# Power_schematic.net
KiCad netlist of a schematic drawn in Altium Designer
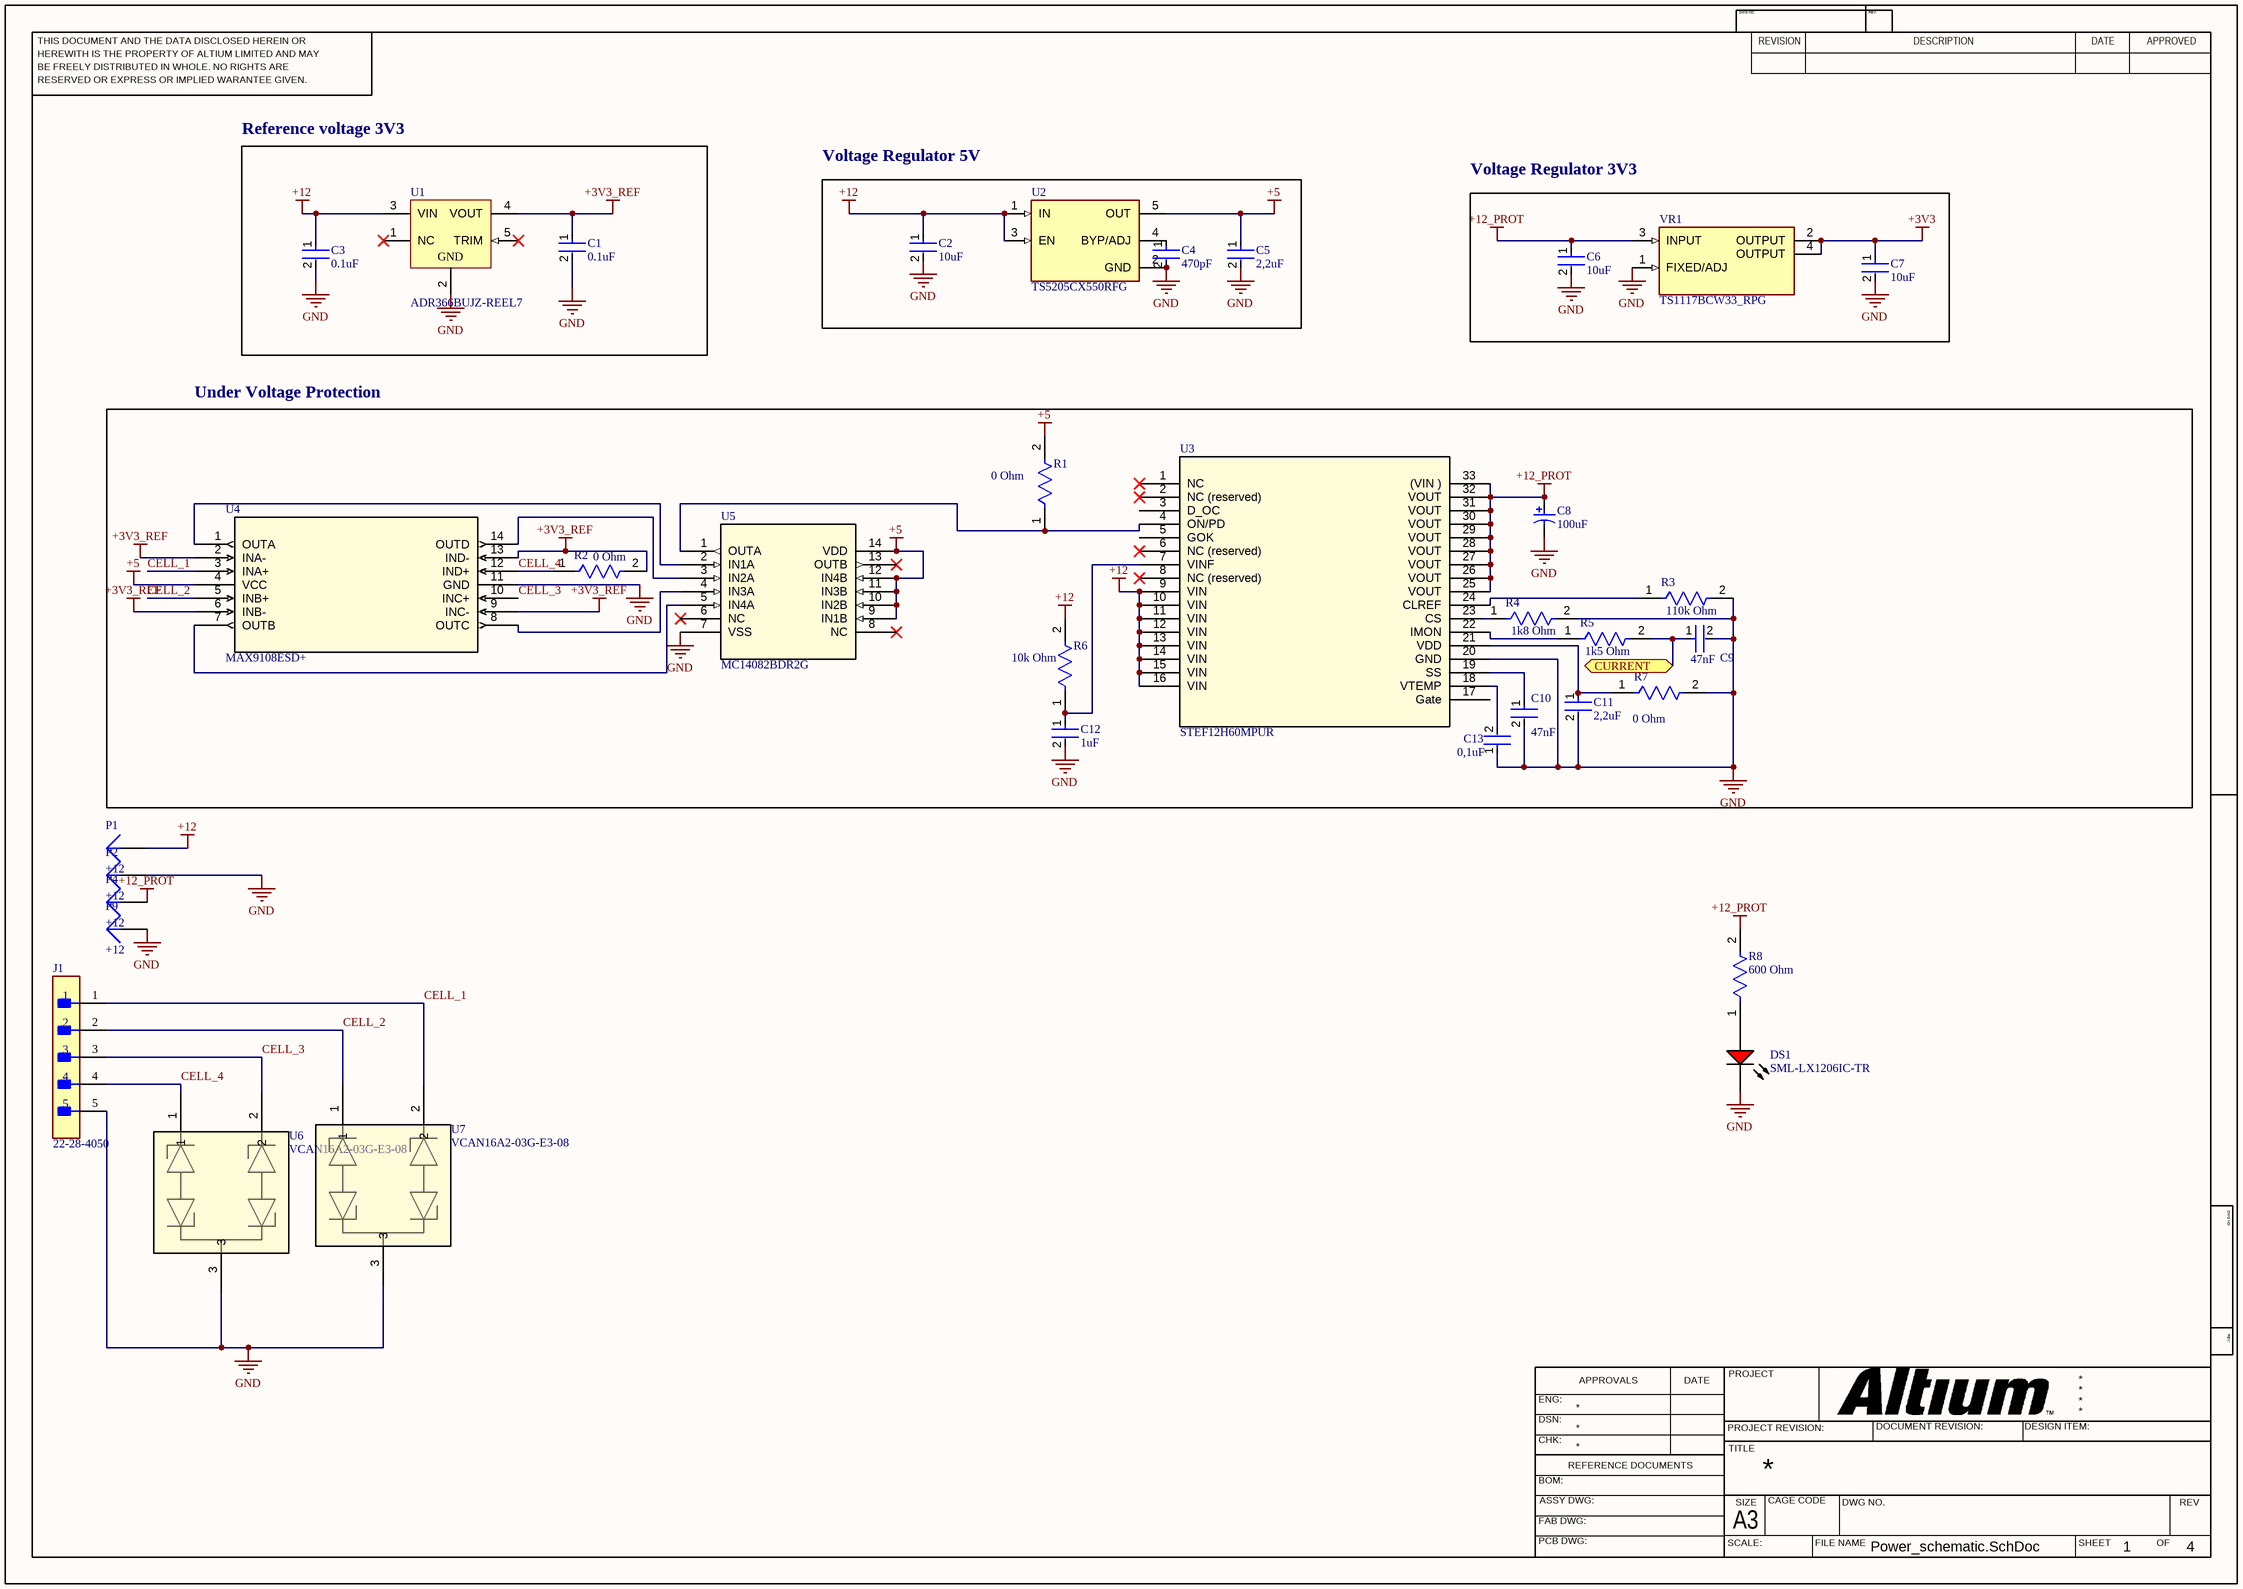
[diagram p0: Power_schematic.SchDoc]

(export (version "E")
  (design (tool "Eeschema 10.0.6"))
  (components
    (comp (ref "C1")
      (value "0.1uF")
      (footprint "FP-CC0805-0_85-MFG")
      (description "CAP CER 0.1UF 50V X7R 0805")
      (fields (field (name "TOLERANCE") "0.1") (field (name "MANUFACTURER PART NUMBER") "CC0805KRX7R9BB104"))
      (libsource (lib "Altium Content Vault") (part "11868f565c42a9108669ba33697ecf6"))
    )
    (comp (ref "C2")
      (value "10uF")
      (footprint "FP-CC0805-0_85-MFG")
      (description "CAP CER 0.1UF 50V X7R 0805")
      (fields (field (name "TOLERANCE") "0.1") (field (name "MANUFACTURER PART NUMBER") "CC0805KRX7R9BB104"))
      (libsource (lib "Altium Content Vault") (part "11868f565c42a9108669ba33697ecf6"))
    )
    (comp (ref "C3")
      (value "0.1uF")
      (footprint "FP-CC0805-0_85-MFG")
      (description "CAP CER 0.1UF 50V X7R 0805")
      (fields (field (name "TOLERANCE") "0.1") (field (name "MANUFACTURER PART NUMBER") "CC0805KRX7R9BB104"))
      (libsource (lib "Altium Content Vault") (part "11868f565c42a9108669ba33697ecf6"))
    )
    (comp (ref "C4")
      (value "470pF")
      (footprint "FP-CC0805-0_85-MFG")
      (description "CAP CER 0.1UF 50V X7R 0805")
      (fields (field (name "TOLERANCE") "0.1") (field (name "MANUFACTURER PART NUMBER") "CC0805KRX7R9BB104"))
      (libsource (lib "Altium Content Vault") (part "11868f565c42a9108669ba33697ecf6"))
    )
    (comp (ref "C5")
      (value "2,2uF")
      (footprint "FP-CC0805-0_85-MFG")
      (description "CAP CER 0.1UF 50V X7R 0805")
      (fields (field (name "TOLERANCE") "0.1") (field (name "MANUFACTURER PART NUMBER") "CC0805KRX7R9BB104"))
      (libsource (lib "Altium Content Vault") (part "11868f565c42a9108669ba33697ecf6"))
    )
    (comp (ref "C6")
      (value "10uF")
      (footprint "FP-CC0805-0_85-MFG")
      (description "CAP CER 0.1UF 50V X7R 0805")
      (fields (field (name "TOLERANCE") "0.1") (field (name "MANUFACTURER PART NUMBER") "CC0805KRX7R9BB104"))
      (libsource (lib "Altium Content Vault") (part "11868f565c42a9108669ba33697ecf6"))
    )
    (comp (ref "C7")
      (value "10uF")
      (footprint "FP-CC0805-0_85-MFG")
      (description "CAP CER 0.1UF 50V X7R 0805")
      (fields (field (name "TOLERANCE") "0.1") (field (name "MANUFACTURER PART NUMBER") "CC0805KRX7R9BB104"))
      (libsource (lib "Altium Content Vault") (part "11868f565c42a9108669ba33697ecf6"))
    )
    (comp (ref "C8")
      (value "100uF")
      (footprint "PNSC-FK-V-D8_V")
      (fields (field (name "MANUFACTURER") "Panasonic"))
      (libsource (lib "Altium Content Vault") (part "CAP-P-2"))
    )
    (comp (ref "C9")
      (value "47nF")
      (footprint "FP-CC0805-0_85-MFG")
      (description "CAP CER 0.1UF 50V X7R 0805")
      (fields (field (name "TOLERANCE") "0.1") (field (name "MANUFACTURER PART NUMBER") "CC0805KRX7R9BB104"))
      (libsource (lib "Altium Content Vault") (part "11868f565c42a9108669ba33697ecf6"))
    )
    (comp (ref "C10")
      (value "47nF")
      (footprint "FP-CC0805-0_85-MFG")
      (description "CAP CER 0.1UF 50V X7R 0805")
      (fields (field (name "TOLERANCE") "0.1") (field (name "MANUFACTURER PART NUMBER") "CC0805KRX7R9BB104"))
      (libsource (lib "Altium Content Vault") (part "11868f565c42a9108669ba33697ecf6"))
    )
    (comp (ref "C11")
      (value "2,2uF")
      (footprint "FP-CC0805-0_85-MFG")
      (description "CAP CER 0.1UF 50V X7R 0805")
      (fields (field (name "TOLERANCE") "0.1") (field (name "MANUFACTURER PART NUMBER") "CC0805KRX7R9BB104"))
      (libsource (lib "Altium Content Vault") (part "11868f565c42a9108669ba33697ecf6"))
    )
    (comp (ref "C12")
      (value "1uF")
      (footprint "FP-CC0805-0_85-MFG")
      (description "CAP CER 0.1UF 50V X7R 0805")
      (fields (field (name "TOLERANCE") "0.1") (field (name "MANUFACTURER PART NUMBER") "CC0805KRX7R9BB104"))
      (libsource (lib "Altium Content Vault") (part "11868f565c42a9108669ba33697ecf6"))
    )
    (comp (ref "C13")
      (value "0,1uF")
      (footprint "FP-CC0805-0_85-MFG")
      (description "CAP CER 0.1UF 50V X7R 0805")
      (fields (field (name "TOLERANCE") "0.1") (field (name "MANUFACTURER PART NUMBER") "CC0805KRX7R9BB104"))
      (libsource (lib "Altium Content Vault") (part "11868f565c42a9108669ba33697ecf6"))
    )
    (comp (ref "DS1")
      (value "SML-LX1206IC-TR")
      (footprint "LUMX-SML-LX1206IC_V")
      (description "LED Red, 65 mW, -40 to 85 degC, 2-Pin SMD, RoHS, Tape and Reel")
      (fields (field (name "MANUFACTURER") "Lumex"))
      (libsource (lib "Altium Content Vault") (part "LED-RED-AK-2"))
    )
    (comp (ref "J1")
      (value "22-28-4050")
      (footprint "FP-22-28-4050-MFG")
      (libsource (lib "Altium Content Vault") (part "bf93c07fd2649a848d0ec8585582aab"))
    )
    (comp (ref "P1")
      (value "+12")
      (footprint "PIN1")
      (description "Plug")
      (fields (field (name "PUBLISHER") "Altium Limited"))
      (libsource (lib "Miscellaneous Connectors") (part "Plug"))
    )
    (comp (ref "P2")
      (value "+12")
      (footprint "PIN1")
      (description "Plug")
      (fields (field (name "PUBLISHER") "Altium Limited"))
      (libsource (lib "Miscellaneous Connectors") (part "Plug"))
    )
    (comp (ref "P4")
      (value "+12")
      (footprint "PIN1")
      (description "Plug")
      (fields (field (name "PUBLISHER") "Altium Limited"))
      (libsource (lib "Miscellaneous Connectors") (part "Plug"))
    )
    (comp (ref "P9")
      (value "+12")
      (footprint "PIN1")
      (description "Plug")
      (fields (field (name "PUBLISHER") "Altium Limited"))
      (libsource (lib "Miscellaneous Connectors") (part "Plug"))
    )
    (comp (ref "R1")
      (value "0 Ohm")
      (footprint "FP-RMCF0805-MFG")
      (description "RES 0 OHM JUMPER 1/8W 0805")
      (libsource (lib "Altium Content Vault") (part "1029c3af85768c4190bb7ad29bc67b5"))
    )
    (comp (ref "R2")
      (value "0 Ohm")
      (footprint "FP-RMCF0805-MFG")
      (description "RES 0 OHM JUMPER 1/8W 0805")
      (libsource (lib "Altium Content Vault") (part "1029c3af85768c4190bb7ad29bc67b5"))
    )
    (comp (ref "R3")
      (value "110k Ohm")
      (footprint "FP-RMCF0805-MFG")
      (description "RES 0 OHM JUMPER 1/8W 0805")
      (libsource (lib "Altium Content Vault") (part "1029c3af85768c4190bb7ad29bc67b5"))
    )
    (comp (ref "R4")
      (value "1k8 Ohm")
      (footprint "FP-RMCF0805-MFG")
      (description "RES 0 OHM JUMPER 1/8W 0805")
      (libsource (lib "Altium Content Vault") (part "1029c3af85768c4190bb7ad29bc67b5"))
    )
    (comp (ref "R5")
      (value "1k5 Ohm")
      (footprint "FP-RMCF0805-MFG")
      (description "RES 0 OHM JUMPER 1/8W 0805")
      (libsource (lib "Altium Content Vault") (part "1029c3af85768c4190bb7ad29bc67b5"))
    )
    (comp (ref "R6")
      (value "10k Ohm")
      (footprint "FP-RMCF0805-MFG")
      (description "RES 0 OHM JUMPER 1/8W 0805")
      (libsource (lib "Altium Content Vault") (part "1029c3af85768c4190bb7ad29bc67b5"))
    )
    (comp (ref "R7")
      (value "0 Ohm")
      (footprint "FP-RMCF0805-MFG")
      (description "RES 0 OHM JUMPER 1/8W 0805")
      (libsource (lib "Altium Content Vault") (part "1029c3af85768c4190bb7ad29bc67b5"))
    )
    (comp (ref "R8")
      (value "600 Ohm")
      (footprint "FP-RMCF0805-MFG")
      (description "RES 0 OHM JUMPER 1/8W 0805")
      (libsource (lib "Altium Content Vault") (part "1029c3af85768c4190bb7ad29bc67b5"))
    )
    (comp (ref "U1")
      (value "ADR366BUJZ-REEL7")
      (footprint "ADI-UJ-5_L")
      (fields (field (name "MANUFACTURER") "Analog Devices"))
      (libsource (lib "Altium Content Vault") (part "ADI-ADR36X-UJ-5"))
    )
    (comp (ref "U2")
      (value "TS5205CX550RFG")
      (footprint "SOT95P270X125-5N")
      (fields (field (name "MF") "{'manufacturer': u'Taiwan Semiconductor Corporation'}"))
      (libsource (lib "TS5205CX550RFG") (part "TS5205CX550RFG"))
    )
    (comp (ref "U3")
      (value "STEF12H60MPUR")
      (footprint "QFN_60MPUR_STM")
      (description "No Description Available")
      (libsource (lib "STEF12H60MPUR") (part "STEF12H60MPUR"))
    )
    (comp (ref "U4")
      (value "MAX9108ESD+")
      (footprint "21-0041B_14")
      (description "No Description Available")
      (libsource (lib "MAX9108ESD&plus_") (part "MAX9108ESD+"))
    )
    (comp (ref "U5")
      (value "MC14082BDR2G")
      (footprint "SOIC-14_NB_ONS")
      (description "No Description Available")
      (libsource (lib "MC14082BDR2G") (part "MC14082BDR2G"))
    )
    (comp (ref "U6")
      (value "VCAN16A2-03G-E3-08")
      (footprint "SOT_3G-E3-08_VIS")
      (description "No Description Available")
      (libsource (lib "VCAN16A2-03G-E3-08") (part "VCAN16A2-03G-E3-08"))
    )
    (comp (ref "U7")
      (value "VCAN16A2-03G-E3-08")
      (footprint "SOT_3G-E3-08_VIS")
      (description "No Description Available")
      (libsource (lib "VCAN16A2-03G-E3-08") (part "VCAN16A2-03G-E3-08"))
    )
    (comp (ref "VR1")
      (value "TS1117BCW33_RPG")
      (footprint "VREG_TS1117BCW50_RPG")
      (fields (field (name "MP") "TS1117BCW50_RPG"))
      (libsource (lib "TS1117BCW50_RPG") (part "TS1117BCW50_RPG"))
    )
  )
  (nets
    (net (code "1") (name "+3V3") (class "Default")
      (node (ref "C7") (pin "1") (pinfunction "1_1") (pintype "passive"))
      (node (ref "VR1") (pin "2") (pinfunction "OUTPUT_2") (pintype "power_in"))
      (node (ref "VR1") (pin "4") (pinfunction "OUTPUT_4") (pintype "power_in"))
    )
    (net (code "2") (name "+3V3_REF") (class "Default")
      (node (ref "C1") (pin "1") (pinfunction "1_1") (pintype "passive"))
      (node (ref "R2") (pin "2") (pinfunction "2_2") (pintype "passive"))
      (node (ref "U1") (pin "4") (pinfunction "VOUT_4") (pintype "power_in"))
      (node (ref "U4") (pin "13") (pinfunction "IND-_13") (pintype "input"))
      (node (ref "U4") (pin "2") (pinfunction "INA-_2") (pintype "input"))
      (node (ref "U4") (pin "6") (pinfunction "INB-_6") (pintype "input"))
      (node (ref "U4") (pin "9") (pinfunction "INC-_9") (pintype "input"))
    )
    (net (code "3") (name "+5") (class "Default")
      (node (ref "C5") (pin "1") (pinfunction "1_1") (pintype "passive"))
      (node (ref "R1") (pin "2") (pinfunction "2_2") (pintype "passive"))
      (node (ref "U2") (pin "5") (pinfunction "OUT_5") (pintype "power_in"))
      (node (ref "U4") (pin "4") (pinfunction "VCC_4") (pintype "power_in"))
      (node (ref "U5") (pin "10") (pinfunction "IN2B_10") (pintype "input"))
      (node (ref "U5") (pin "11") (pinfunction "IN3B_11") (pintype "input"))
      (node (ref "U5") (pin "12") (pinfunction "IN4B_12") (pintype "input"))
      (node (ref "U5") (pin "14") (pinfunction "VDD_14") (pintype "power_in"))
      (node (ref "U5") (pin "9") (pinfunction "IN1B_9") (pintype "input"))
    )
    (net (code "4") (name "+12") (class "Default")
      (node (ref "C2") (pin "1") (pinfunction "1_1") (pintype "passive"))
      (node (ref "C3") (pin "1") (pinfunction "1_1") (pintype "passive"))
      (node (ref "P1") (pin "1") (pinfunction "1_1") (pintype "passive"))
      (node (ref "R6") (pin "2") (pinfunction "2_2") (pintype "passive"))
      (node (ref "U1") (pin "3") (pinfunction "VIN_3") (pintype "power_in"))
      (node (ref "U2") (pin "1") (pinfunction "IN_1") (pintype "input"))
      (node (ref "U2") (pin "3") (pinfunction "EN_3") (pintype "input"))
      (node (ref "U3") (pin "10") (pinfunction "VIN_10") (pintype "passive"))
      (node (ref "U3") (pin "11") (pinfunction "VIN_11") (pintype "passive"))
      (node (ref "U3") (pin "12") (pinfunction "VIN_12") (pintype "passive"))
      (node (ref "U3") (pin "13") (pinfunction "VIN_13") (pintype "passive"))
      (node (ref "U3") (pin "14") (pinfunction "VIN_14") (pintype "passive"))
      (node (ref "U3") (pin "15") (pinfunction "VIN_15") (pintype "passive"))
      (node (ref "U3") (pin "16") (pinfunction "VIN_16") (pintype "passive"))
      (node (ref "U3") (pin "9") (pinfunction "VIN_9") (pintype "passive"))
    )
    (net (code "5") (name "+12_PROT") (class "Default")
      (node (ref "C6") (pin "1") (pinfunction "1_1") (pintype "passive"))
      (node (ref "C8") (pin "1") (pinfunction "1_1") (pintype "passive"))
      (node (ref "P4") (pin "1") (pinfunction "1_1") (pintype "passive"))
      (node (ref "R8") (pin "2") (pinfunction "2_2") (pintype "passive"))
      (node (ref "U3") (pin "25") (pinfunction "VOUT_25") (pintype "power_in"))
      (node (ref "U3") (pin "26") (pinfunction "VOUT_26") (pintype "power_in"))
      (node (ref "U3") (pin "27") (pinfunction "VOUT_27") (pintype "power_in"))
      (node (ref "U3") (pin "28") (pinfunction "VOUT_28") (pintype "power_in"))
      (node (ref "U3") (pin "29") (pinfunction "VOUT_29") (pintype "power_in"))
      (node (ref "U3") (pin "30") (pinfunction "VOUT_30") (pintype "power_in"))
      (node (ref "U3") (pin "31") (pinfunction "VOUT_31") (pintype "power_in"))
      (node (ref "U3") (pin "32") (pinfunction "VOUT_32") (pintype "power_in"))
      (node (ref "U3") (pin "33") (pinfunction "(VIN_)_33") (pintype "passive"))
      (node (ref "VR1") (pin "3") (pinfunction "INPUT_3") (pintype "input"))
    )
    (net (code "6") (name "/CELL_1") (class "Default")
      (node (ref "J1") (pin "1") (pinfunction "1_1") (pintype "passive"))
      (node (ref "U4") (pin "3") (pinfunction "INA+_3") (pintype "input"))
      (node (ref "U7") (pin "2") (pinfunction "2_2") (pintype "passive"))
    )
    (net (code "7") (name "/CELL_2") (class "Default")
      (node (ref "J1") (pin "2") (pinfunction "2_2") (pintype "passive"))
      (node (ref "U4") (pin "5") (pinfunction "INB+_5") (pintype "input"))
      (node (ref "U7") (pin "1") (pinfunction "1_1") (pintype "passive"))
    )
    (net (code "8") (name "/CELL_3") (class "Default")
      (node (ref "J1") (pin "3") (pinfunction "3_3") (pintype "passive"))
      (node (ref "U4") (pin "10") (pinfunction "INC+_10") (pintype "input"))
      (node (ref "U6") (pin "2") (pinfunction "2_2") (pintype "passive"))
    )
    (net (code "9") (name "/CELL_4") (class "Default")
      (node (ref "J1") (pin "4") (pinfunction "4_4") (pintype "passive"))
      (node (ref "R2") (pin "1") (pinfunction "1_1") (pintype "passive"))
      (node (ref "U4") (pin "12") (pinfunction "IND+_12") (pintype "input"))
      (node (ref "U6") (pin "1") (pinfunction "1_1") (pintype "passive"))
    )
    (net (code "10") (name "/CURRENT") (class "Default")
      (node (ref "C9") (pin "1") (pinfunction "1_1") (pintype "passive"))
      (node (ref "R5") (pin "2") (pinfunction "2_2") (pintype "passive"))
    )
    (net (code "11") (name "GND") (class "Default")
      (node (ref "C1") (pin "2") (pinfunction "2_2") (pintype "passive"))
      (node (ref "C10") (pin "2") (pinfunction "2_2") (pintype "passive"))
      (node (ref "C11") (pin "2") (pinfunction "2_2") (pintype "passive"))
      (node (ref "C12") (pin "2") (pinfunction "2_2") (pintype "passive"))
      (node (ref "C13") (pin "1") (pinfunction "1_1") (pintype "passive"))
      (node (ref "C2") (pin "2") (pinfunction "2_2") (pintype "passive"))
      (node (ref "C3") (pin "2") (pinfunction "2_2") (pintype "passive"))
      (node (ref "C4") (pin "2") (pinfunction "2_2") (pintype "passive"))
      (node (ref "C5") (pin "2") (pinfunction "2_2") (pintype "passive"))
      (node (ref "C6") (pin "2") (pinfunction "2_2") (pintype "passive"))
      (node (ref "C7") (pin "2") (pinfunction "2_2") (pintype "passive"))
      (node (ref "C8") (pin "2") (pinfunction "2_2") (pintype "passive"))
      (node (ref "C9") (pin "2") (pinfunction "2_2") (pintype "passive"))
      (node (ref "DS1") (pin "2") (pinfunction "K_2") (pintype "passive"))
      (node (ref "J1") (pin "5") (pinfunction "5_5") (pintype "passive"))
      (node (ref "P2") (pin "1") (pinfunction "1_1") (pintype "passive"))
      (node (ref "P9") (pin "1") (pinfunction "1_1") (pintype "passive"))
      (node (ref "R3") (pin "2") (pinfunction "2_2") (pintype "passive"))
      (node (ref "R4") (pin "2") (pinfunction "2_2") (pintype "passive"))
      (node (ref "R7") (pin "2") (pinfunction "2_2") (pintype "passive"))
      (node (ref "U1") (pin "2") (pinfunction "GND_2") (pintype "power_in"))
      (node (ref "U2") (pin "2") (pinfunction "GND_2") (pintype "power_in"))
      (node (ref "U3") (pin "20") (pinfunction "GND_20") (pintype "power_in"))
      (node (ref "U4") (pin "11") (pinfunction "GND_11") (pintype "power_in"))
      (node (ref "U5") (pin "7") (pinfunction "VSS_7") (pintype "power_in"))
      (node (ref "U6") (pin "3") (pinfunction "3_3") (pintype "passive"))
      (node (ref "U7") (pin "3") (pinfunction "3_3") (pintype "passive"))
      (node (ref "VR1") (pin "1") (pinfunction "FIXED/ADJ_1") (pintype "input"))
    )
    (net (code "12") (name "Net-(DS1-A)") (class "Default")
      (node (ref "DS1") (pin "1") (pinfunction "A_1") (pintype "passive"))
      (node (ref "R8") (pin "1") (pinfunction "1_1") (pintype "passive"))
    )
    (net (code "13") (name "Net-(U2-BYP{slash}ADJ)") (class "Default")
      (node (ref "C4") (pin "1") (pinfunction "1_1") (pintype "passive"))
      (node (ref "U2") (pin "4") (pinfunction "BYP/ADJ_4") (pintype "passive"))
    )
    (net (code "14") (name "Net-(U3-CLREF)") (class "Default")
      (node (ref "R3") (pin "1") (pinfunction "1_1") (pintype "passive"))
      (node (ref "U3") (pin "24") (pinfunction "CLREF_24") (pintype "passive"))
    )
    (net (code "15") (name "Net-(U3-CS)") (class "Default")
      (node (ref "R4") (pin "1") (pinfunction "1_1") (pintype "passive"))
      (node (ref "U3") (pin "23") (pinfunction "CS_23") (pintype "passive"))
    )
    (net (code "16") (name "Net-(U3-IMON)") (class "Default")
      (node (ref "R5") (pin "1") (pinfunction "1_1") (pintype "passive"))
      (node (ref "U3") (pin "22") (pinfunction "IMON_22") (pintype "passive"))
    )
    (net (code "17") (name "Net-(U3-ON{slash}PD)") (class "Default")
      (node (ref "R1") (pin "1") (pinfunction "1_1") (pintype "passive"))
      (node (ref "U3") (pin "4") (pinfunction "ON/PD_4") (pintype "passive"))
      (node (ref "U5") (pin "1") (pinfunction "OUTA_1") (pintype "output"))
    )
    (net (code "18") (name "Net-(U3-SS)") (class "Default")
      (node (ref "C10") (pin "1") (pinfunction "1_1") (pintype "passive"))
      (node (ref "U3") (pin "19") (pinfunction "SS_19") (pintype "passive"))
    )
    (net (code "19") (name "Net-(U3-VDD)") (class "Default")
      (node (ref "C11") (pin "1") (pinfunction "1_1") (pintype "passive"))
      (node (ref "R7") (pin "1") (pinfunction "1_1") (pintype "passive"))
      (node (ref "U3") (pin "21") (pinfunction "VDD_21") (pintype "power_in"))
    )
    (net (code "20") (name "Net-(U3-VINF)") (class "Default")
      (node (ref "C12") (pin "1") (pinfunction "1_1") (pintype "passive"))
      (node (ref "R6") (pin "1") (pinfunction "1_1") (pintype "passive"))
      (node (ref "U3") (pin "7") (pinfunction "VINF_7") (pintype "passive"))
    )
    (net (code "21") (name "Net-(U3-VTEMP)") (class "Default")
      (node (ref "C13") (pin "2") (pinfunction "2_2") (pintype "passive"))
      (node (ref "U3") (pin "18") (pinfunction "VTEMP_18") (pintype "passive"))
    )
    (net (code "22") (name "Net-(U4-OUTA)") (class "Default")
      (node (ref "U4") (pin "1") (pinfunction "OUTA_1") (pintype "output"))
      (node (ref "U5") (pin "2") (pinfunction "IN1A_2") (pintype "input"))
    )
    (net (code "23") (name "Net-(U4-OUTB)") (class "Default")
      (node (ref "U4") (pin "7") (pinfunction "OUTB_7") (pintype "output"))
      (node (ref "U5") (pin "5") (pinfunction "IN4A_5") (pintype "input"))
    )
    (net (code "24") (name "Net-(U4-OUTC)") (class "Default")
      (node (ref "U4") (pin "8") (pinfunction "OUTC_8") (pintype "output"))
      (node (ref "U5") (pin "4") (pinfunction "IN3A_4") (pintype "input"))
    )
    (net (code "25") (name "Net-(U4-OUTD)") (class "Default")
      (node (ref "U4") (pin "14") (pinfunction "OUTD_14") (pintype "output"))
      (node (ref "U5") (pin "3") (pinfunction "IN2A_3") (pintype "input"))
    )
    (net (code "26") (name "unconnected-(U1-NC-Pad1)") (class "Default")
      (node (ref "U1") (pin "1") (pinfunction "NC_1") (pintype "passive+no_connect"))
    )
    (net (code "27") (name "unconnected-(U1-TRIM-Pad5)") (class "Default")
      (node (ref "U1") (pin "5") (pinfunction "TRIM_5") (pintype "input+no_connect"))
    )
    (net (code "28") (name "unconnected-(U3-D_OC-Pad3)") (class "Default")
      (node (ref "U3") (pin "3") (pinfunction "D_OC_3") (pintype "passive"))
    )
    (net (code "29") (name "unconnected-(U3-GOK-Pad5)") (class "Default")
      (node (ref "U3") (pin "5") (pinfunction "GOK_5") (pintype "passive"))
    )
    (net (code "30") (name "unconnected-(U3-Gate-Pad17)") (class "Default")
      (node (ref "U3") (pin "17") (pinfunction "Gate_17") (pintype "passive"))
    )
    (net (code "31") (name "unconnected-(U3-NC-Pad1)") (class "Default")
      (node (ref "U3") (pin "1") (pinfunction "NC_1") (pintype "passive+no_connect"))
    )
    (net (code "32") (name "unconnected-(U3-NC_(reserved)-Pad2)") (class "Default")
      (node (ref "U3") (pin "2") (pinfunction "NC_(reserved)_2") (pintype "passive+no_connect"))
    )
    (net (code "33") (name "unconnected-(U3-NC_(reserved)-Pad6)") (class "Default")
      (node (ref "U3") (pin "6") (pinfunction "NC_(reserved)_6") (pintype "passive+no_connect"))
    )
    (net (code "34") (name "unconnected-(U3-NC_(reserved)-Pad8)") (class "Default")
      (node (ref "U3") (pin "8") (pinfunction "NC_(reserved)_8") (pintype "passive+no_connect"))
    )
    (net (code "35") (name "unconnected-(U5-NC-Pad6)") (class "Default")
      (node (ref "U5") (pin "6") (pinfunction "NC_6") (pintype "passive+no_connect"))
    )
    (net (code "36") (name "unconnected-(U5-NC-Pad8)") (class "Default")
      (node (ref "U5") (pin "8") (pinfunction "NC_8") (pintype "passive+no_connect"))
    )
    (net (code "37") (name "unconnected-(U5-OUTB-Pad13)") (class "Default")
      (node (ref "U5") (pin "13") (pinfunction "OUTB_13") (pintype "output+no_connect"))
    )
  )
)
